# CPLD.net
KiCad netlist of a schematic drawn in Altium Designer
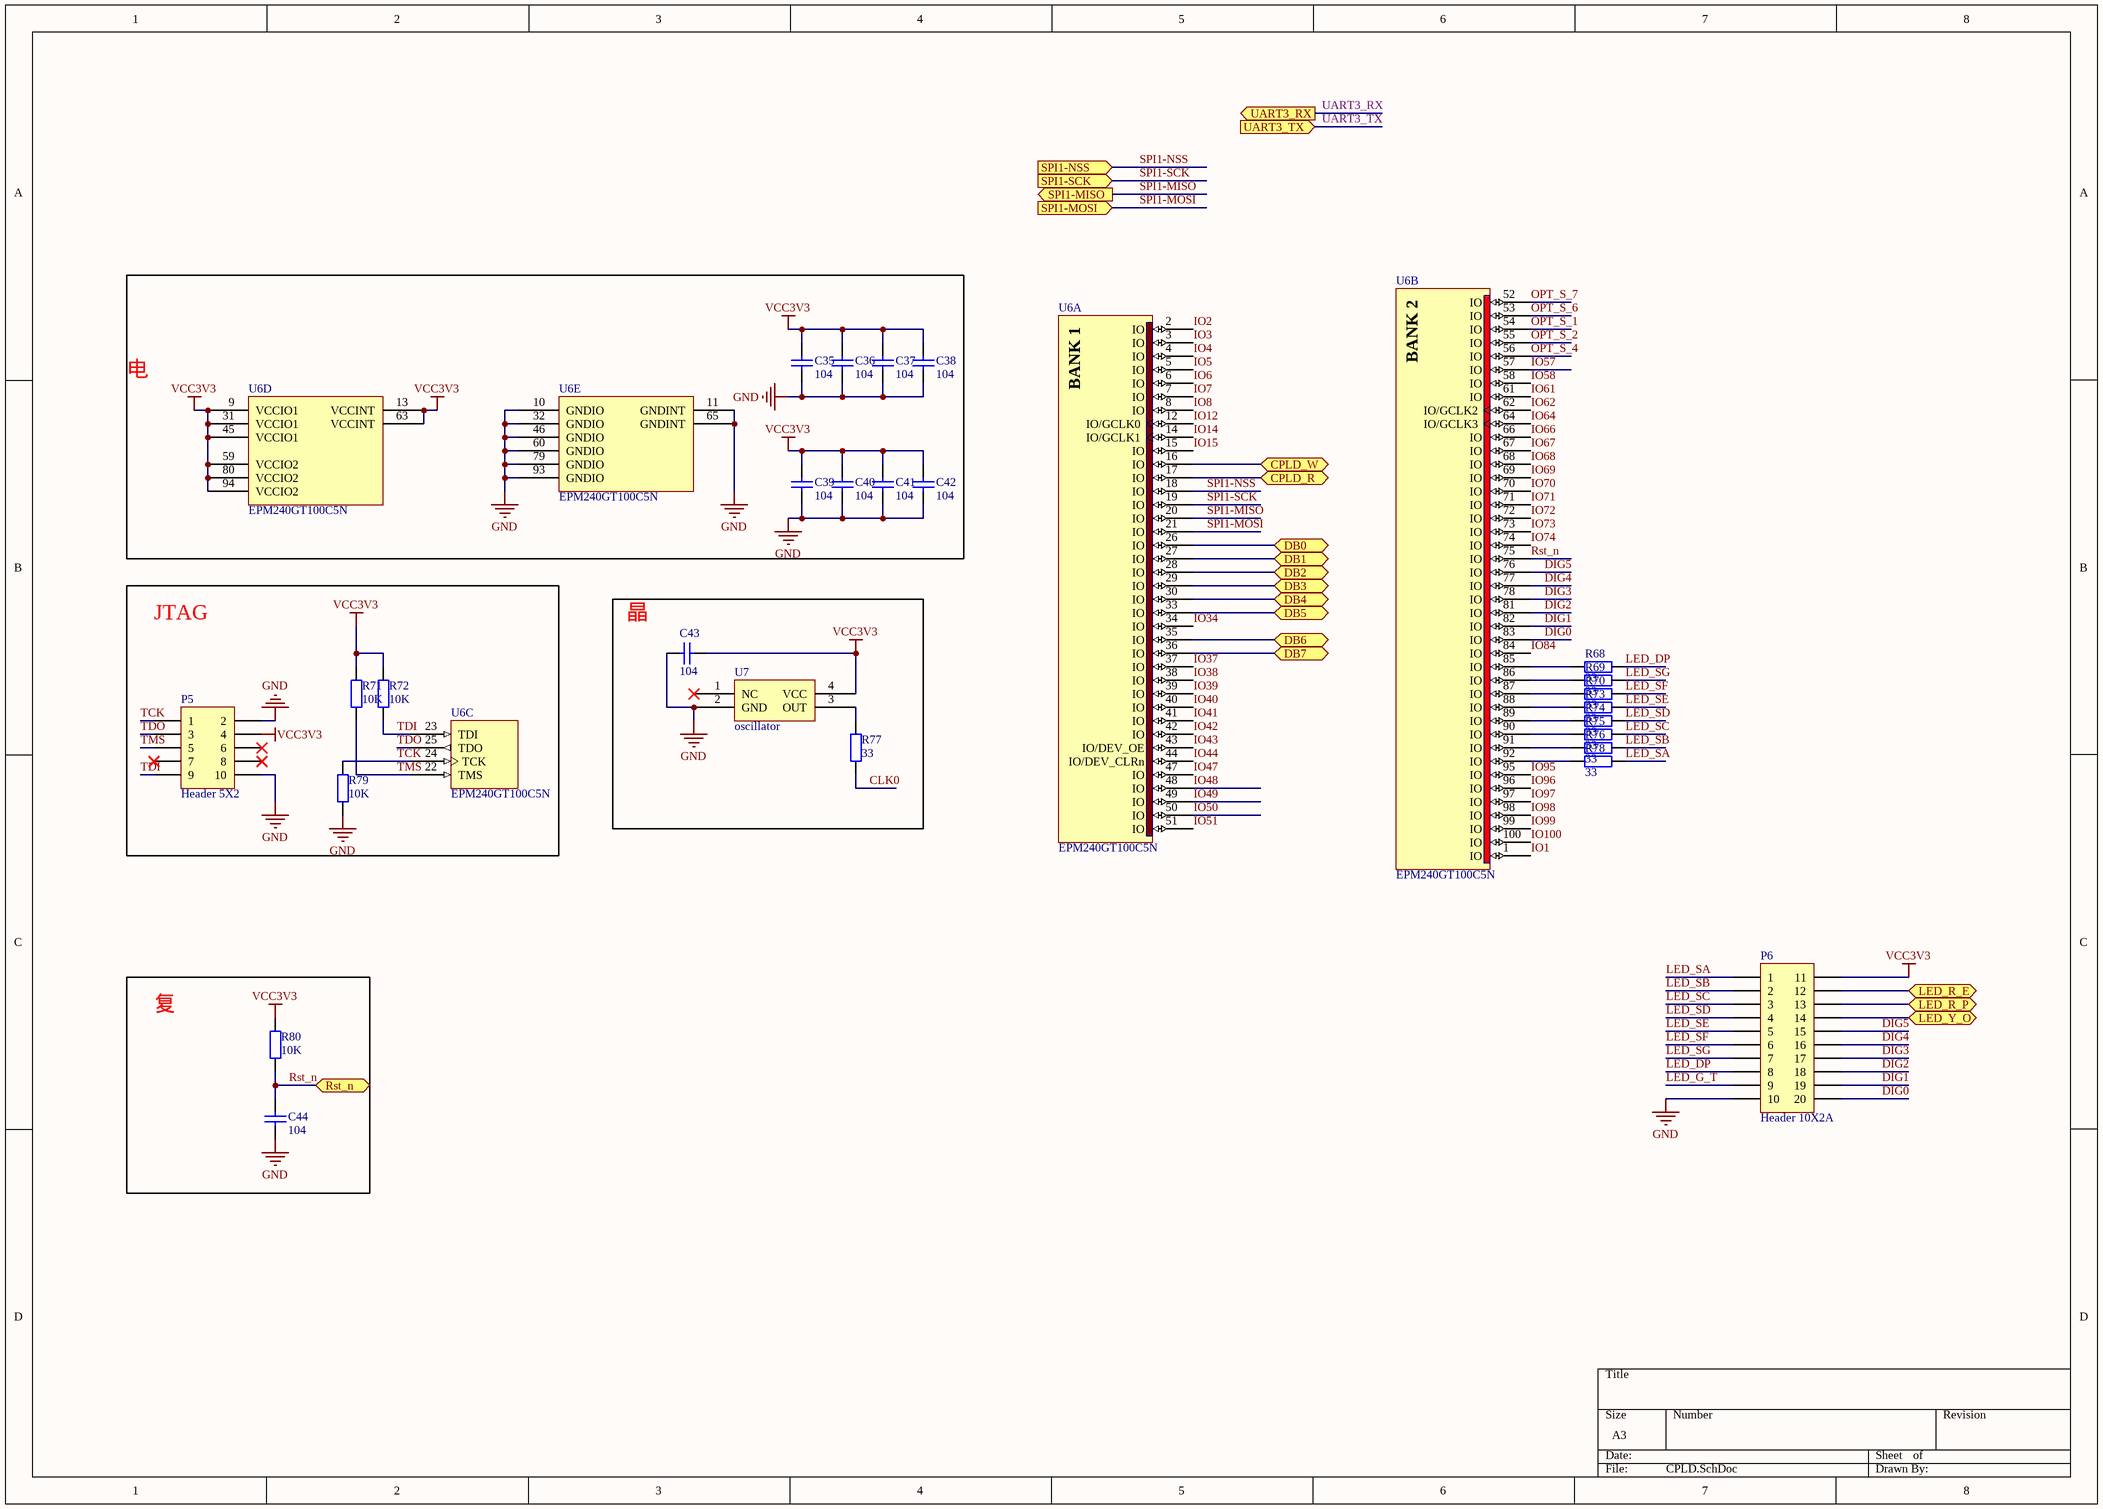
[diagram p0: CPLD.SchDoc]

(export (version "E")
  (design (tool "Eeschema 10.0.6"))
  (components
    (comp (ref "C35")
      (value "104")
      (footprint "C0805")
      (description "Capacitor")
      (fields (field (name "Comment") "Cap") (field (name "PUBLISHER") "Altium Limited"))
      (libsource (lib "Miscellaneous Devices") (part "Cap"))
    )
    (comp (ref "C36")
      (value "104")
      (footprint "C0805")
      (description "Capacitor")
      (fields (field (name "Comment") "Cap") (field (name "PUBLISHER") "Altium Limited"))
      (libsource (lib "Miscellaneous Devices") (part "Cap"))
    )
    (comp (ref "C37")
      (value "104")
      (footprint "C0805")
      (description "Capacitor")
      (fields (field (name "Comment") "Cap") (field (name "PUBLISHER") "Altium Limited"))
      (libsource (lib "Miscellaneous Devices") (part "Cap"))
    )
    (comp (ref "C38")
      (value "104")
      (footprint "C0805")
      (description "Capacitor")
      (fields (field (name "Comment") "Cap") (field (name "PUBLISHER") "Altium Limited"))
      (libsource (lib "Miscellaneous Devices") (part "Cap"))
    )
    (comp (ref "C39")
      (value "104")
      (footprint "C0805")
      (description "Capacitor")
      (fields (field (name "Comment") "Cap") (field (name "PUBLISHER") "Altium Limited"))
      (libsource (lib "Miscellaneous Devices") (part "Cap"))
    )
    (comp (ref "C40")
      (value "104")
      (footprint "C0805")
      (description "Capacitor")
      (fields (field (name "Comment") "Cap") (field (name "PUBLISHER") "Altium Limited"))
      (libsource (lib "Miscellaneous Devices") (part "Cap"))
    )
    (comp (ref "C41")
      (value "104")
      (footprint "C0805")
      (description "Capacitor")
      (fields (field (name "Comment") "Cap") (field (name "PUBLISHER") "Altium Limited"))
      (libsource (lib "Miscellaneous Devices") (part "Cap"))
    )
    (comp (ref "C42")
      (value "104")
      (footprint "C0805")
      (description "Capacitor")
      (fields (field (name "Comment") "Cap") (field (name "PUBLISHER") "Altium Limited"))
      (libsource (lib "Miscellaneous Devices") (part "Cap"))
    )
    (comp (ref "C43")
      (value "104")
      (footprint "C0805")
      (description "Capacitor")
      (fields (field (name "Comment") "Cap") (field (name "PUBLISHER") "Altium Limited"))
      (libsource (lib "Miscellaneous Devices") (part "Cap"))
    )
    (comp (ref "C44")
      (value "104")
      (footprint "C0805")
      (description "Capacitor")
      (fields (field (name "Comment") "Cap") (field (name "PUBLISHER") "Altium Limited"))
      (libsource (lib "Miscellaneous Devices") (part "Cap"))
    )
    (comp (ref "P5")
      (value "Header 5X2")
      (footprint "HDR2X5")
      (description "Header, 5-Pin, Dual row")
      (fields (field (name "PUBLISHER") "Altium Limited"))
      (libsource (lib "Miscellaneous Connectors") (part "Header 5X2"))
    )
    (comp (ref "P6")
      (value "Header 10X2A")
      (footprint "HDR2X10_CEN")
      (description "Header, 10-Pin, Dual row")
      (fields (field (name "PUBLISHER") "Altium Limited"))
      (libsource (lib "Miscellaneous Connectors") (part "Header 10X2A"))
    )
    (comp (ref "R68")
      (value "33")
      (footprint "R0805")
      (description "Resistor")
      (fields (field (name "Comment") "Res2") (field (name "PUBLISHER") "Altium Limited"))
      (libsource (lib "") (part "Res2_1"))
    )
    (comp (ref "R69")
      (value "33")
      (footprint "R0805")
      (description "Resistor")
      (fields (field (name "Comment") "Res2") (field (name "PUBLISHER") "Altium Limited"))
      (libsource (lib "") (part "Res2_1"))
    )
    (comp (ref "R70")
      (value "33")
      (footprint "R0805")
      (description "Resistor")
      (fields (field (name "Comment") "Res2") (field (name "PUBLISHER") "Altium Limited"))
      (libsource (lib "") (part "Res2_1"))
    )
    (comp (ref "R71")
      (value "10K")
      (footprint "R0805")
      (description "Resistor")
      (fields (field (name "Comment") "Res2") (field (name "PUBLISHER") "Altium Limited"))
      (libsource (lib "Miscellaneous Devices") (part "Res2"))
    )
    (comp (ref "R72")
      (value "10K")
      (footprint "R0805")
      (description "Resistor")
      (fields (field (name "Comment") "Res2") (field (name "PUBLISHER") "Altium Limited"))
      (libsource (lib "Miscellaneous Devices") (part "Res2"))
    )
    (comp (ref "R73")
      (value "33")
      (footprint "R0805")
      (description "Resistor")
      (fields (field (name "Comment") "Res2") (field (name "PUBLISHER") "Altium Limited"))
      (libsource (lib "") (part "Res2_1"))
    )
    (comp (ref "R74")
      (value "33")
      (footprint "R0805")
      (description "Resistor")
      (fields (field (name "Comment") "Res2") (field (name "PUBLISHER") "Altium Limited"))
      (libsource (lib "") (part "Res2_1"))
    )
    (comp (ref "R75")
      (value "33")
      (footprint "R0805")
      (description "Resistor")
      (fields (field (name "Comment") "Res2") (field (name "PUBLISHER") "Altium Limited"))
      (libsource (lib "") (part "Res2_1"))
    )
    (comp (ref "R76")
      (value "33")
      (footprint "R0805")
      (description "Resistor")
      (fields (field (name "Comment") "Res2") (field (name "PUBLISHER") "Altium Limited"))
      (libsource (lib "") (part "Res2_1"))
    )
    (comp (ref "R77")
      (value "33")
      (footprint "R0805")
      (description "Resistor")
      (fields (field (name "Comment") "Res2") (field (name "PUBLISHER") "Altium Limited"))
      (libsource (lib "Miscellaneous Devices") (part "Res2"))
    )
    (comp (ref "R78")
      (value "33")
      (footprint "R0805")
      (description "Resistor")
      (fields (field (name "Comment") "Res2") (field (name "PUBLISHER") "Altium Limited"))
      (libsource (lib "") (part "Res2_1"))
    )
    (comp (ref "R79")
      (value "10K")
      (footprint "R0805")
      (description "Resistor")
      (fields (field (name "Comment") "Res2") (field (name "PUBLISHER") "Altium Limited"))
      (libsource (lib "Miscellaneous Devices") (part "Res2"))
    )
    (comp (ref "R80")
      (value "10K")
      (footprint "R0805")
      (description "Resistor")
      (fields (field (name "Comment") "Res2") (field (name "PUBLISHER") "Altium Limited"))
      (libsource (lib "Miscellaneous Devices") (part "Res2"))
    )
    (comp (ref "U6")
      (value "EPM240GT100C5N")
      (footprint "TQFP100_N")
      (fields (field (name "PUBLISHER") "Altium Limited"))
      (libsource (lib "Altera MAX II") (part "EPM240GT100C5N"))
    )
    (comp (ref "U7") (value "oscillator") (footprint "JZ") (libsource (lib "Schlib1") (part "oscillator")))
  )
  (nets
    (net (code "1") (name "/CLK0") (class "Default")
      (node (ref "R77") (pin "1") (pinfunction "1_1") (pintype "passive"))
    )
    (net (code "2") (name "/CPLD_R") (class "Default")
      (node (ref "U6") (pin "17") (pinfunction "IO_17") (pintype "bidirectional"))
    )
    (net (code "3") (name "/CPLD_W") (class "Default")
      (node (ref "U6") (pin "16") (pinfunction "IO_16") (pintype "bidirectional"))
    )
    (net (code "4") (name "/DB0") (class "Default")
      (node (ref "U6") (pin "26") (pinfunction "IO_26") (pintype "bidirectional"))
    )
    (net (code "5") (name "/DB1") (class "Default")
      (node (ref "U6") (pin "27") (pinfunction "IO_27") (pintype "bidirectional"))
    )
    (net (code "6") (name "/DB2") (class "Default")
      (node (ref "U6") (pin "28") (pinfunction "IO_28") (pintype "bidirectional"))
    )
    (net (code "7") (name "/DB3") (class "Default")
      (node (ref "U6") (pin "29") (pinfunction "IO_29") (pintype "bidirectional"))
    )
    (net (code "8") (name "/DB4") (class "Default")
      (node (ref "U6") (pin "30") (pinfunction "IO_30") (pintype "bidirectional"))
    )
    (net (code "9") (name "/DB5") (class "Default")
      (node (ref "U6") (pin "33") (pinfunction "IO_33") (pintype "bidirectional"))
    )
    (net (code "10") (name "/DB6") (class "Default")
      (node (ref "U6") (pin "35") (pinfunction "IO_35") (pintype "bidirectional"))
    )
    (net (code "11") (name "/DB7") (class "Default")
      (node (ref "U6") (pin "36") (pinfunction "IO_36") (pintype "bidirectional"))
    )
    (net (code "12") (name "/DIG0") (class "Default")
      (node (ref "P6") (pin "20") (pinfunction "20_20") (pintype "passive"))
      (node (ref "U6") (pin "83") (pinfunction "IO_83") (pintype "bidirectional"))
    )
    (net (code "13") (name "/DIG1") (class "Default")
      (node (ref "P6") (pin "19") (pinfunction "19_19") (pintype "passive"))
      (node (ref "U6") (pin "82") (pinfunction "IO_82") (pintype "bidirectional"))
    )
    (net (code "14") (name "/DIG2") (class "Default")
      (node (ref "P6") (pin "18") (pinfunction "18_18") (pintype "passive"))
      (node (ref "U6") (pin "81") (pinfunction "IO_81") (pintype "bidirectional"))
    )
    (net (code "15") (name "/DIG3") (class "Default")
      (node (ref "P6") (pin "17") (pinfunction "17_17") (pintype "passive"))
      (node (ref "U6") (pin "78") (pinfunction "IO_78") (pintype "bidirectional"))
    )
    (net (code "16") (name "/DIG4") (class "Default")
      (node (ref "P6") (pin "16") (pinfunction "16_16") (pintype "passive"))
      (node (ref "U6") (pin "77") (pinfunction "IO_77") (pintype "bidirectional"))
    )
    (net (code "17") (name "/DIG5") (class "Default")
      (node (ref "P6") (pin "15") (pinfunction "15_15") (pintype "passive"))
      (node (ref "U6") (pin "76") (pinfunction "IO_76") (pintype "bidirectional"))
    )
    (net (code "18") (name "/IO1") (class "Default")
      (node (ref "U6") (pin "1") (pinfunction "IO_1") (pintype "bidirectional"))
    )
    (net (code "19") (name "/IO2") (class "Default")
      (node (ref "U6") (pin "2") (pinfunction "IO_2") (pintype "bidirectional"))
    )
    (net (code "20") (name "/IO3") (class "Default")
      (node (ref "U6") (pin "3") (pinfunction "IO_3") (pintype "bidirectional"))
    )
    (net (code "21") (name "/IO4") (class "Default")
      (node (ref "U6") (pin "4") (pinfunction "IO_4") (pintype "bidirectional"))
    )
    (net (code "22") (name "/IO5") (class "Default")
      (node (ref "U6") (pin "5") (pinfunction "IO_5") (pintype "bidirectional"))
    )
    (net (code "23") (name "/IO6") (class "Default")
      (node (ref "U6") (pin "6") (pinfunction "IO_6") (pintype "bidirectional"))
    )
    (net (code "24") (name "/IO7") (class "Default")
      (node (ref "U6") (pin "7") (pinfunction "IO_7") (pintype "bidirectional"))
    )
    (net (code "25") (name "/IO8") (class "Default")
      (node (ref "U6") (pin "8") (pinfunction "IO_8") (pintype "bidirectional"))
    )
    (net (code "26") (name "/IO12") (class "Default")
      (node (ref "U6") (pin "12") (pinfunction "IO/GCLK0_12") (pintype "bidirectional"))
    )
    (net (code "27") (name "/IO14") (class "Default")
      (node (ref "U6") (pin "14") (pinfunction "IO/GCLK1_14") (pintype "bidirectional"))
    )
    (net (code "28") (name "/IO15") (class "Default")
      (node (ref "U6") (pin "15") (pinfunction "IO_15") (pintype "bidirectional"))
    )
    (net (code "29") (name "/IO34") (class "Default")
      (node (ref "U6") (pin "34") (pinfunction "IO_34") (pintype "bidirectional"))
    )
    (net (code "30") (name "/IO37") (class "Default")
      (node (ref "U6") (pin "37") (pinfunction "IO_37") (pintype "bidirectional"))
    )
    (net (code "31") (name "/IO38") (class "Default")
      (node (ref "U6") (pin "38") (pinfunction "IO_38") (pintype "bidirectional"))
    )
    (net (code "32") (name "/IO39") (class "Default")
      (node (ref "U6") (pin "39") (pinfunction "IO_39") (pintype "bidirectional"))
    )
    (net (code "33") (name "/IO40") (class "Default")
      (node (ref "U6") (pin "40") (pinfunction "IO_40") (pintype "bidirectional"))
    )
    (net (code "34") (name "/IO41") (class "Default")
      (node (ref "U6") (pin "41") (pinfunction "IO_41") (pintype "bidirectional"))
    )
    (net (code "35") (name "/IO42") (class "Default")
      (node (ref "U6") (pin "42") (pinfunction "IO_42") (pintype "bidirectional"))
    )
    (net (code "36") (name "/IO43") (class "Default")
      (node (ref "U6") (pin "43") (pinfunction "IO/DEV_OE_43") (pintype "bidirectional"))
    )
    (net (code "37") (name "/IO44") (class "Default")
      (node (ref "U6") (pin "44") (pinfunction "IO/DEV_CLRn_44") (pintype "bidirectional"))
    )
    (net (code "38") (name "/IO47") (class "Default")
      (node (ref "U6") (pin "47") (pinfunction "IO_47") (pintype "bidirectional"))
    )
    (net (code "39") (name "/IO48") (class "Default")
      (node (ref "U6") (pin "48") (pinfunction "IO_48") (pintype "bidirectional"))
    )
    (net (code "40") (name "/IO49") (class "Default")
      (node (ref "U6") (pin "49") (pinfunction "IO_49") (pintype "bidirectional"))
    )
    (net (code "41") (name "/IO50") (class "Default")
      (node (ref "U6") (pin "50") (pinfunction "IO_50") (pintype "bidirectional"))
    )
    (net (code "42") (name "/IO51") (class "Default")
      (node (ref "U6") (pin "51") (pinfunction "IO_51") (pintype "bidirectional"))
    )
    (net (code "43") (name "/IO57") (class "Default")
      (node (ref "U6") (pin "57") (pinfunction "IO_57") (pintype "bidirectional"))
    )
    (net (code "44") (name "/IO58") (class "Default")
      (node (ref "U6") (pin "58") (pinfunction "IO_58") (pintype "bidirectional"))
    )
    (net (code "45") (name "/IO61") (class "Default")
      (node (ref "U6") (pin "61") (pinfunction "IO_61") (pintype "bidirectional"))
    )
    (net (code "46") (name "/IO62") (class "Default")
      (node (ref "U6") (pin "62") (pinfunction "IO/GCLK2_62") (pintype "bidirectional"))
    )
    (net (code "47") (name "/IO64") (class "Default")
      (node (ref "U6") (pin "64") (pinfunction "IO/GCLK3_64") (pintype "bidirectional"))
    )
    (net (code "48") (name "/IO66") (class "Default")
      (node (ref "U6") (pin "66") (pinfunction "IO_66") (pintype "bidirectional"))
    )
    (net (code "49") (name "/IO67") (class "Default")
      (node (ref "U6") (pin "67") (pinfunction "IO_67") (pintype "bidirectional"))
    )
    (net (code "50") (name "/IO68") (class "Default")
      (node (ref "U6") (pin "68") (pinfunction "IO_68") (pintype "bidirectional"))
    )
    (net (code "51") (name "/IO69") (class "Default")
      (node (ref "U6") (pin "69") (pinfunction "IO_69") (pintype "bidirectional"))
    )
    (net (code "52") (name "/IO70") (class "Default")
      (node (ref "U6") (pin "70") (pinfunction "IO_70") (pintype "bidirectional"))
    )
    (net (code "53") (name "/IO71") (class "Default")
      (node (ref "U6") (pin "71") (pinfunction "IO_71") (pintype "bidirectional"))
    )
    (net (code "54") (name "/IO72") (class "Default")
      (node (ref "U6") (pin "72") (pinfunction "IO_72") (pintype "bidirectional"))
    )
    (net (code "55") (name "/IO73") (class "Default")
      (node (ref "U6") (pin "73") (pinfunction "IO_73") (pintype "bidirectional"))
    )
    (net (code "56") (name "/IO74") (class "Default")
      (node (ref "U6") (pin "74") (pinfunction "IO_74") (pintype "bidirectional"))
    )
    (net (code "57") (name "/IO84") (class "Default")
      (node (ref "U6") (pin "84") (pinfunction "IO_84") (pintype "bidirectional"))
    )
    (net (code "58") (name "/IO95") (class "Default")
      (node (ref "U6") (pin "95") (pinfunction "IO_95") (pintype "bidirectional"))
    )
    (net (code "59") (name "/IO96") (class "Default")
      (node (ref "U6") (pin "96") (pinfunction "IO_96") (pintype "bidirectional"))
    )
    (net (code "60") (name "/IO97") (class "Default")
      (node (ref "U6") (pin "97") (pinfunction "IO_97") (pintype "bidirectional"))
    )
    (net (code "61") (name "/IO98") (class "Default")
      (node (ref "U6") (pin "98") (pinfunction "IO_98") (pintype "bidirectional"))
    )
    (net (code "62") (name "/IO99") (class "Default")
      (node (ref "U6") (pin "99") (pinfunction "IO_99") (pintype "bidirectional"))
    )
    (net (code "63") (name "/IO100") (class "Default")
      (node (ref "U6") (pin "100") (pinfunction "IO_100") (pintype "bidirectional"))
    )
    (net (code "64") (name "/LED_DP") (class "Default")
      (node (ref "P6") (pin "8") (pinfunction "8_8") (pintype "passive"))
      (node (ref "R68") (pin "1") (pinfunction "1_1") (pintype "passive"))
    )
    (net (code "65") (name "/LED_G_T") (class "Default")
      (node (ref "P6") (pin "9") (pinfunction "9_9") (pintype "passive"))
    )
    (net (code "66") (name "/LED_R_E") (class "Default")
      (node (ref "P6") (pin "12") (pinfunction "12_12") (pintype "passive"))
    )
    (net (code "67") (name "/LED_R_P") (class "Default")
      (node (ref "P6") (pin "13") (pinfunction "13_13") (pintype "passive"))
    )
    (net (code "68") (name "/LED_SA") (class "Default")
      (node (ref "P6") (pin "1") (pinfunction "1_1") (pintype "passive"))
      (node (ref "R78") (pin "1") (pinfunction "1_1") (pintype "passive"))
    )
    (net (code "69") (name "/LED_SB") (class "Default")
      (node (ref "P6") (pin "2") (pinfunction "2_2") (pintype "passive"))
      (node (ref "R76") (pin "1") (pinfunction "1_1") (pintype "passive"))
    )
    (net (code "70") (name "/LED_SC") (class "Default")
      (node (ref "P6") (pin "3") (pinfunction "3_3") (pintype "passive"))
      (node (ref "R75") (pin "1") (pinfunction "1_1") (pintype "passive"))
    )
    (net (code "71") (name "/LED_SD") (class "Default")
      (node (ref "P6") (pin "4") (pinfunction "4_4") (pintype "passive"))
      (node (ref "R74") (pin "1") (pinfunction "1_1") (pintype "passive"))
    )
    (net (code "72") (name "/LED_SE") (class "Default")
      (node (ref "P6") (pin "5") (pinfunction "5_5") (pintype "passive"))
      (node (ref "R73") (pin "1") (pinfunction "1_1") (pintype "passive"))
    )
    (net (code "73") (name "/LED_SF") (class "Default")
      (node (ref "P6") (pin "6") (pinfunction "6_6") (pintype "passive"))
      (node (ref "R70") (pin "1") (pinfunction "1_1") (pintype "passive"))
    )
    (net (code "74") (name "/LED_SG") (class "Default")
      (node (ref "P6") (pin "7") (pinfunction "7_7") (pintype "passive"))
      (node (ref "R69") (pin "1") (pinfunction "1_1") (pintype "passive"))
    )
    (net (code "75") (name "/LED_Y_O") (class "Default")
      (node (ref "P6") (pin "14") (pinfunction "14_14") (pintype "passive"))
    )
    (net (code "76") (name "/OPT_S_1") (class "Default")
      (node (ref "U6") (pin "54") (pinfunction "IO_54") (pintype "bidirectional"))
    )
    (net (code "77") (name "/OPT_S_2") (class "Default")
      (node (ref "U6") (pin "55") (pinfunction "IO_55") (pintype "bidirectional"))
    )
    (net (code "78") (name "/OPT_S_4") (class "Default")
      (node (ref "U6") (pin "56") (pinfunction "IO_56") (pintype "bidirectional"))
    )
    (net (code "79") (name "/OPT_S_6") (class "Default")
      (node (ref "U6") (pin "53") (pinfunction "IO_53") (pintype "bidirectional"))
    )
    (net (code "80") (name "/OPT_S_7") (class "Default")
      (node (ref "U6") (pin "52") (pinfunction "IO_52") (pintype "bidirectional"))
    )
    (net (code "81") (name "/Rst_n") (class "Default")
      (node (ref "C44") (pin "2") (pinfunction "2_2") (pintype "passive"))
      (node (ref "R80") (pin "1") (pinfunction "1_1") (pintype "passive"))
      (node (ref "U6") (pin "75") (pinfunction "IO_75") (pintype "bidirectional"))
    )
    (net (code "82") (name "/SPI1-MISO") (class "Default")
      (node (ref "U6") (pin "20") (pinfunction "IO_20") (pintype "bidirectional"))
    )
    (net (code "83") (name "/SPI1-MOSI") (class "Default")
      (node (ref "U6") (pin "21") (pinfunction "IO_21") (pintype "bidirectional"))
    )
    (net (code "84") (name "/SPI1-NSS") (class "Default")
      (node (ref "U6") (pin "18") (pinfunction "IO_18") (pintype "bidirectional"))
    )
    (net (code "85") (name "/SPI1-SCK") (class "Default")
      (node (ref "U6") (pin "19") (pinfunction "IO_19") (pintype "bidirectional"))
    )
    (net (code "86") (name "/TCK") (class "Default")
      (node (ref "P5") (pin "1") (pinfunction "1_1") (pintype "passive"))
      (node (ref "R79") (pin "2") (pinfunction "2_2") (pintype "passive"))
      (node (ref "U6") (pin "24") (pinfunction "TCK_24") (pintype "input"))
    )
    (net (code "87") (name "/TDI") (class "Default")
      (node (ref "P5") (pin "9") (pinfunction "9_9") (pintype "passive"))
      (node (ref "R72") (pin "1") (pinfunction "1_1") (pintype "passive"))
      (node (ref "U6") (pin "23") (pinfunction "TDI_23") (pintype "input"))
    )
    (net (code "88") (name "/TDO") (class "Default")
      (node (ref "P5") (pin "3") (pinfunction "3_3") (pintype "passive"))
      (node (ref "U6") (pin "25") (pinfunction "TDO_25") (pintype "output"))
    )
    (net (code "89") (name "/TMS") (class "Default")
      (node (ref "P5") (pin "5") (pinfunction "5_5") (pintype "passive"))
      (node (ref "R71") (pin "1") (pinfunction "1_1") (pintype "passive"))
      (node (ref "U6") (pin "22") (pinfunction "TMS_22") (pintype "input"))
    )
    (net (code "92") (name "GND") (class "Default")
      (node (ref "C35") (pin "1") (pinfunction "1_1") (pintype "passive"))
      (node (ref "C36") (pin "1") (pinfunction "1_1") (pintype "passive"))
      (node (ref "C37") (pin "1") (pinfunction "1_1") (pintype "passive"))
      (node (ref "C38") (pin "1") (pinfunction "1_1") (pintype "passive"))
      (node (ref "C39") (pin "1") (pinfunction "1_1") (pintype "passive"))
      (node (ref "C40") (pin "1") (pinfunction "1_1") (pintype "passive"))
      (node (ref "C41") (pin "1") (pinfunction "1_1") (pintype "passive"))
      (node (ref "C42") (pin "1") (pinfunction "1_1") (pintype "passive"))
      (node (ref "C43") (pin "1") (pinfunction "1_1") (pintype "passive"))
      (node (ref "C44") (pin "1") (pinfunction "1_1") (pintype "passive"))
      (node (ref "P5") (pin "10") (pinfunction "10_10") (pintype "passive"))
      (node (ref "P5") (pin "2") (pinfunction "2_2") (pintype "passive"))
      (node (ref "P6") (pin "10") (pinfunction "10_10") (pintype "passive"))
      (node (ref "R79") (pin "1") (pinfunction "1_1") (pintype "passive"))
      (node (ref "U6") (pin "10") (pinfunction "GNDIO_10") (pintype "power_in"))
      (node (ref "U6") (pin "11") (pinfunction "GNDINT_11") (pintype "power_in"))
      (node (ref "U6") (pin "32") (pinfunction "GNDIO_32") (pintype "power_in"))
      (node (ref "U6") (pin "46") (pinfunction "GNDIO_46") (pintype "power_in"))
      (node (ref "U6") (pin "60") (pinfunction "GNDIO_60") (pintype "power_in"))
      (node (ref "U6") (pin "65") (pinfunction "GNDINT_65") (pintype "power_in"))
      (node (ref "U6") (pin "79") (pinfunction "GNDIO_79") (pintype "power_in"))
      (node (ref "U6") (pin "93") (pinfunction "GNDIO_93") (pintype "power_in"))
      (node (ref "U7") (pin "2") (pinfunction "GND_2") (pintype "passive"))
    )
    (net (code "93") (name "Net-(R68-Pad2)") (class "Default")
      (node (ref "R68") (pin "2") (pinfunction "2_2") (pintype "passive"))
      (node (ref "U6") (pin "85") (pinfunction "IO_85") (pintype "bidirectional"))
    )
    (net (code "94") (name "Net-(R69-Pad2)") (class "Default")
      (node (ref "R69") (pin "2") (pinfunction "2_2") (pintype "passive"))
      (node (ref "U6") (pin "86") (pinfunction "IO_86") (pintype "bidirectional"))
    )
    (net (code "95") (name "Net-(R70-Pad2)") (class "Default")
      (node (ref "R70") (pin "2") (pinfunction "2_2") (pintype "passive"))
      (node (ref "U6") (pin "87") (pinfunction "IO_87") (pintype "bidirectional"))
    )
    (net (code "96") (name "Net-(R73-Pad2)") (class "Default")
      (node (ref "R73") (pin "2") (pinfunction "2_2") (pintype "passive"))
      (node (ref "U6") (pin "88") (pinfunction "IO_88") (pintype "bidirectional"))
    )
    (net (code "97") (name "Net-(R74-Pad2)") (class "Default")
      (node (ref "R74") (pin "2") (pinfunction "2_2") (pintype "passive"))
      (node (ref "U6") (pin "89") (pinfunction "IO_89") (pintype "bidirectional"))
    )
    (net (code "98") (name "Net-(R75-Pad2)") (class "Default")
      (node (ref "R75") (pin "2") (pinfunction "2_2") (pintype "passive"))
      (node (ref "U6") (pin "90") (pinfunction "IO_90") (pintype "bidirectional"))
    )
    (net (code "99") (name "Net-(R76-Pad2)") (class "Default")
      (node (ref "R76") (pin "2") (pinfunction "2_2") (pintype "passive"))
      (node (ref "U6") (pin "91") (pinfunction "IO_91") (pintype "bidirectional"))
    )
    (net (code "100") (name "Net-(R78-Pad2)") (class "Default")
      (node (ref "R78") (pin "2") (pinfunction "2_2") (pintype "passive"))
      (node (ref "U6") (pin "92") (pinfunction "IO_92") (pintype "bidirectional"))
    )
    (net (code "101") (name "Net-(U7-OUT)") (class "Default")
      (node (ref "R77") (pin "2") (pinfunction "2_2") (pintype "passive"))
      (node (ref "U7") (pin "3") (pinfunction "OUT_3") (pintype "passive"))
    )
    (net (code "102") (name "VCC3V3") (class "Default")
      (node (ref "C35") (pin "2") (pinfunction "2_2") (pintype "passive"))
      (node (ref "C36") (pin "2") (pinfunction "2_2") (pintype "passive"))
      (node (ref "C37") (pin "2") (pinfunction "2_2") (pintype "passive"))
      (node (ref "C38") (pin "2") (pinfunction "2_2") (pintype "passive"))
      (node (ref "C39") (pin "2") (pinfunction "2_2") (pintype "passive"))
      (node (ref "C40") (pin "2") (pinfunction "2_2") (pintype "passive"))
      (node (ref "C41") (pin "2") (pinfunction "2_2") (pintype "passive"))
      (node (ref "C42") (pin "2") (pinfunction "2_2") (pintype "passive"))
      (node (ref "C43") (pin "2") (pinfunction "2_2") (pintype "passive"))
      (node (ref "P5") (pin "4") (pinfunction "4_4") (pintype "passive"))
      (node (ref "P6") (pin "11") (pinfunction "11_11") (pintype "passive"))
      (node (ref "R71") (pin "2") (pinfunction "2_2") (pintype "passive"))
      (node (ref "R72") (pin "2") (pinfunction "2_2") (pintype "passive"))
      (node (ref "R80") (pin "2") (pinfunction "2_2") (pintype "passive"))
      (node (ref "U6") (pin "13") (pinfunction "VCCINT_13") (pintype "power_in"))
      (node (ref "U6") (pin "31") (pinfunction "VCCIO1_31") (pintype "power_in"))
      (node (ref "U6") (pin "45") (pinfunction "VCCIO1_45") (pintype "power_in"))
      (node (ref "U6") (pin "59") (pinfunction "VCCIO2_59") (pintype "power_in"))
      (node (ref "U6") (pin "63") (pinfunction "VCCINT_63") (pintype "power_in"))
      (node (ref "U6") (pin "80") (pinfunction "VCCIO2_80") (pintype "power_in"))
      (node (ref "U6") (pin "9") (pinfunction "VCCIO1_9") (pintype "power_in"))
      (node (ref "U6") (pin "94") (pinfunction "VCCIO2_94") (pintype "power_in"))
      (node (ref "U7") (pin "4") (pinfunction "VCC_4") (pintype "passive"))
    )
    (net (code "103") (name "unconnected-(P5-Pad6)") (class "Default")
      (node (ref "P5") (pin "6") (pinfunction "6_6") (pintype "passive+no_connect"))
    )
    (net (code "104") (name "unconnected-(P5-Pad7)") (class "Default")
      (node (ref "P5") (pin "7") (pinfunction "7_7") (pintype "passive+no_connect"))
    )
    (net (code "105") (name "unconnected-(P5-Pad8)") (class "Default")
      (node (ref "P5") (pin "8") (pinfunction "8_8") (pintype "passive+no_connect"))
    )
    (net (code "106") (name "unconnected-(U7-NC-Pad1)") (class "Default")
      (node (ref "U7") (pin "1") (pinfunction "NC_1") (pintype "passive+no_connect"))
    )
  )
)
